# invamp.net
KiCad netlist of a schematic drawn in EAGLE
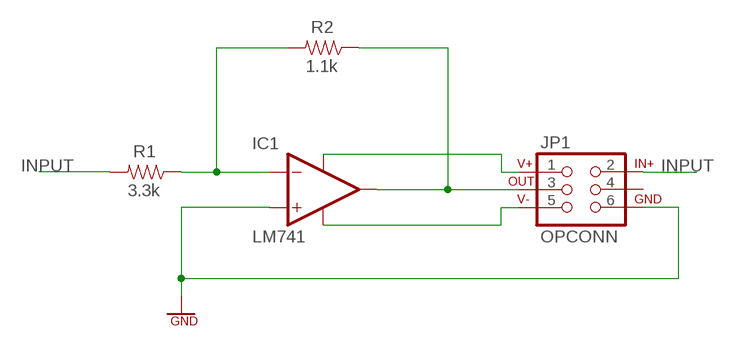
[diagram p0: schematic, sheet 1]

(export (version "E")
  (design (tool "Eeschema 10.0.6"))
  (components
    (comp (ref "IC1")
      (value "LM741")
      (footprint "eagle-import:SO08")
      (libsource (lib "eagle-import") (part "LM741"))
    )
    (comp (ref "JP1")
      (value "OPCONN")
      (footprint "eagle-import:2X3")
      (libsource (lib "eagle-import") (part "OPCONN"))
    )
    (comp (ref "R1")
      (value "3.3k")
      (footprint "eagle-import:SMD0603")
      (libsource (lib "eagle-import") (part "RES_0603"))
    )
    (comp (ref "R2")
      (value "1.1k")
      (footprint "eagle-import:SMD0603")
      (libsource (lib "eagle-import") (part "RES_0603"))
    )
  )
  (nets
    (net (code "1") (name "/INPUT") (class "Default")
      (node (ref "JP1") (pin "2") (pinfunction "2_2") (pintype "passive"))
      (node (ref "R1") (pin "2") (pinfunction "2_2") (pintype "passive"))
    )
    (net (code "2") (name "GND") (class "Default")
      (node (ref "IC1") (pin "3") (pinfunction "IN+_3") (pintype "input"))
      (node (ref "JP1") (pin "6") (pinfunction "6_6") (pintype "passive"))
    )
    (net (code "3") (name "Net-(IC1-IN-)") (class "Default")
      (node (ref "IC1") (pin "2") (pinfunction "IN-_2") (pintype "input"))
      (node (ref "R1") (pin "1") (pinfunction "1_1") (pintype "passive"))
      (node (ref "R2") (pin "2") (pinfunction "2_2") (pintype "passive"))
    )
    (net (code "4") (name "Net-(IC1-OUT)") (class "Default")
      (node (ref "IC1") (pin "6") (pinfunction "OUT_6") (pintype "output"))
      (node (ref "JP1") (pin "3") (pinfunction "3_3") (pintype "passive"))
      (node (ref "R2") (pin "1") (pinfunction "1_1") (pintype "passive"))
    )
    (net (code "5") (name "Net-(IC1-V+)") (class "Default")
      (node (ref "IC1") (pin "7") (pinfunction "V+_7") (pintype "power_in"))
      (node (ref "JP1") (pin "1") (pinfunction "1_1") (pintype "passive"))
    )
    (net (code "6") (name "Net-(IC1-V-)") (class "Default")
      (node (ref "IC1") (pin "4") (pinfunction "V-_4") (pintype "power_in"))
      (node (ref "JP1") (pin "5") (pinfunction "5_5") (pintype "passive"))
    )
    (net (code "7") (name "unconnected-(JP1-Pad4)") (class "Default")
      (node (ref "JP1") (pin "4") (pinfunction "4_4") (pintype "passive"))
    )
  )
)
